# ATMEGA328.net
KiCad netlist of a schematic drawn in Altium Designer
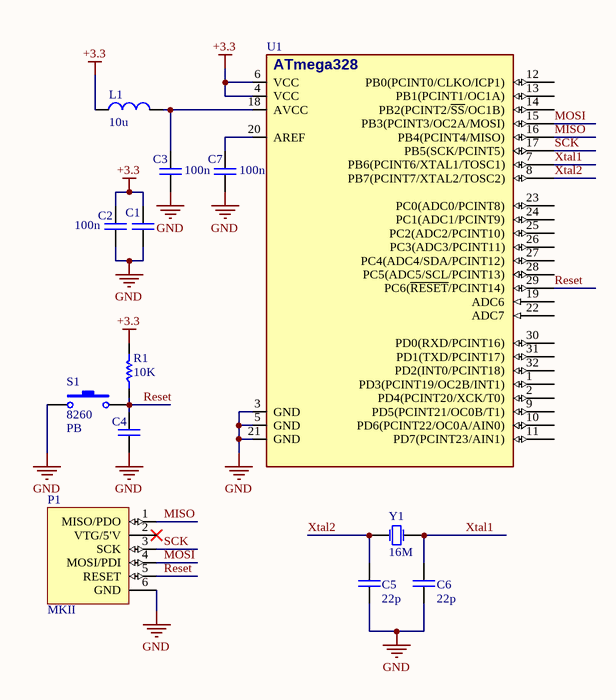
[diagram p0: ATMEGA328.SchDoc]

(export (version "E")
  (design (tool "Eeschema 10.0.6"))
  (components
    (comp (ref "C1")
      (value "100n")
      (footprint "CAP 0805/2012")
      (description "Bipolar ceramic capacitor SMD")
      (fields (field (name "VALIDATION") "Valid"))
      (libsource (lib "aKaReZa") (part "Cap_Multi_SMD_100nF_0805"))
    )
    (comp (ref "C2")
      (value "100n")
      (footprint "CAP 0805/2012")
      (description "Bipolar ceramic capacitor SMD")
      (fields (field (name "VALIDATION") "Valid"))
      (libsource (lib "aKaReZa") (part "Cap_Multi_SMD_100nF_0805"))
    )
    (comp (ref "C3")
      (value "100n")
      (footprint "CAP 0805/2012")
      (description "Bipolar ceramic capacitor SMD")
      (fields (field (name "VALIDATION") "Valid"))
      (libsource (lib "aKaReZa") (part "Cap_Multi_SMD_100nF_0805"))
    )
    (comp (ref "C4")
      (value "100n")
      (footprint "CAP 0805/2012")
      (description "Bipolar ceramic capacitor SMD")
      (fields (field (name "VALIDATION") "Valid"))
      (libsource (lib "aKaReZa") (part "Cap_Multi_SMD_100nF_0805"))
    )
    (comp (ref "C5")
      (value "22p")
      (footprint "CAP 0805/2012")
      (description "Bipolar ceramic capacitor SMD")
      (fields (field (name "VALIDATION") "Valid"))
      (libsource (lib "aKaReZa") (part "Cap_Multi_SMD_0805"))
    )
    (comp (ref "C6")
      (value "22p")
      (footprint "CAP 0805/2012")
      (description "Bipolar ceramic capacitor SMD")
      (fields (field (name "VALIDATION") "Valid"))
      (libsource (lib "aKaReZa") (part "Cap_Multi_SMD_0805"))
    )
    (comp (ref "C7")
      (value "100n")
      (footprint "CAP 0805/2012")
      (description "Bipolar ceramic capacitor SMD")
      (fields (field (name "VALIDATION") "Valid"))
      (libsource (lib "aKaReZa") (part "Cap_Multi_SMD_100nF_0805"))
    )
    (comp (ref "L1")
      (value "10u")
      (footprint "IND0805")
      (description "Inductor")
      (fields (field (name "VALIDATION") "Valid"))
      (libsource (lib "aKaReZa") (part "Ind_SMD_0805"))
    )
    (comp (ref "P1")
      (value "3x2")
      (footprint "IDC_2X3")
      (description "6 Pin Standard ISP Header For MKII")
      (fields (field (name "TYPE") "MKII") (field (name "VALIDATION") "NT"))
      (libsource (lib "aKaReZa") (part "Con_Prog_MKII_ISP"))
    )
    (comp (ref "R1")
      (value "10K")
      (footprint "RES 0805 (2012X06L)")
      (description "Resistor")
      (fields (field (name "VALIDATION") "Valid"))
      (libsource (lib "aKaReZa") (part "Res_SMD_0805"))
    )
    (comp (ref "S1")
      (value "PB")
      (footprint "SW_PB_SMD_2PIN_SPST_6X3X2")
      (description "SMT Tactile ‎Switch")
      (fields (field (name "INFLOW") "8260") (field (name "VALIDATION") "Valid"))
      (libsource (lib "aKaReZa") (part "SW_PushButton_2_SMD"))
    )
    (comp (ref "U1")
      (value "ATmega328P")
      (footprint "QFG50_48")
      (description "8-Bit AVR Microcontroller with 32K Bytes of In-System Programmable Flash Memory")
      (fields (field (name "VALIDATION") "Valid"))
      (libsource (lib "aKaReZa") (part "IC_MCU_ATmega328P_SMD"))
    )
    (comp (ref "Y1")
      (value "16M")
      (footprint "Crystal SMD")
      (description "Crystal Oscillator")
      (fields (field (name "VALIDATION") "Valid"))
      (libsource (lib "aKaReZa") (part "Other_Elec_Xtal_SMD"))
    )
  )
  (nets
    (net (code "1") (name "+3.3") (class "Default")
      (node (ref "C1") (pin "1") (pinfunction "1_1") (pintype "passive"))
      (node (ref "C2") (pin "1") (pinfunction "1_1") (pintype "passive"))
      (node (ref "L1") (pin "1") (pinfunction "1_1") (pintype "passive"))
      (node (ref "R1") (pin "2") (pinfunction "2_2") (pintype "passive"))
      (node (ref "U1") (pin "4") (pinfunction "VCC_4") (pintype "power_in"))
      (node (ref "U1") (pin "6") (pinfunction "VCC_6") (pintype "power_in"))
    )
    (net (code "2") (name "/MISO") (class "Default")
      (node (ref "P1") (pin "1") (pinfunction "MISO/PDO_1") (pintype "bidirectional"))
      (node (ref "U1") (pin "16") (pinfunction "PB4(PCINT4/MISO)_16") (pintype "bidirectional"))
    )
    (net (code "3") (name "/MOSI") (class "Default")
      (node (ref "P1") (pin "4") (pinfunction "MOSI/PDI_4") (pintype "bidirectional"))
      (node (ref "U1") (pin "15") (pinfunction "PB3(PCINT3/OC2A/MOSI)_15") (pintype "bidirectional"))
    )
    (net (code "4") (name "/Reset") (class "Default")
      (node (ref "C4") (pin "1") (pinfunction "1_1") (pintype "passive"))
      (node (ref "P1") (pin "5") (pinfunction "RESET_5") (pintype "bidirectional"))
      (node (ref "R1") (pin "1") (pinfunction "1_1") (pintype "passive"))
      (node (ref "S1") (pin "2") (pinfunction "2_2") (pintype "passive"))
      (node (ref "U1") (pin "29") (pinfunction "PC6(~{RESET}/PCINT14)_29") (pintype "bidirectional"))
    )
    (net (code "5") (name "/SCK") (class "Default")
      (node (ref "P1") (pin "3") (pinfunction "SCK_3") (pintype "bidirectional"))
      (node (ref "U1") (pin "17") (pinfunction "PB5(SCK/PCINT5)_17") (pintype "bidirectional"))
    )
    (net (code "6") (name "/Xtal1") (class "Default")
      (node (ref "C6") (pin "1") (pinfunction "1_1") (pintype "passive"))
      (node (ref "U1") (pin "7") (pinfunction "PB6(PCINT6/XTAL1/TOSC1)_7") (pintype "bidirectional"))
      (node (ref "Y1") (pin "2") (pinfunction "OSC2_2") (pintype "passive"))
    )
    (net (code "7") (name "/Xtal2") (class "Default")
      (node (ref "C5") (pin "1") (pinfunction "1_1") (pintype "passive"))
      (node (ref "U1") (pin "8") (pinfunction "PB7(PCINT7/XTAL2/TOSC2)_8") (pintype "bidirectional"))
      (node (ref "Y1") (pin "1") (pinfunction "OSC1_1") (pintype "passive"))
    )
    (net (code "8") (name "GND") (class "Default")
      (node (ref "C1") (pin "2") (pinfunction "2_2") (pintype "passive"))
      (node (ref "C2") (pin "2") (pinfunction "2_2") (pintype "passive"))
      (node (ref "C3") (pin "2") (pinfunction "2_2") (pintype "passive"))
      (node (ref "C4") (pin "2") (pinfunction "2_2") (pintype "passive"))
      (node (ref "C5") (pin "2") (pinfunction "2_2") (pintype "passive"))
      (node (ref "C6") (pin "2") (pinfunction "2_2") (pintype "passive"))
      (node (ref "C7") (pin "2") (pinfunction "2_2") (pintype "passive"))
      (node (ref "P1") (pin "6") (pinfunction "GND_6") (pintype "passive"))
      (node (ref "S1") (pin "1") (pinfunction "1_1") (pintype "passive"))
      (node (ref "U1") (pin "21") (pinfunction "GND_21") (pintype "power_in"))
      (node (ref "U1") (pin "3") (pinfunction "GND_3") (pintype "power_in"))
      (node (ref "U1") (pin "5") (pinfunction "GND_5") (pintype "power_in"))
    )
    (net (code "9") (name "Net-(U1-AREF)") (class "Default")
      (node (ref "C7") (pin "1") (pinfunction "1_1") (pintype "passive"))
      (node (ref "U1") (pin "20") (pinfunction "AREF_20") (pintype "passive"))
    )
    (net (code "10") (name "Net-(U1-AVCC)") (class "Default")
      (node (ref "C3") (pin "1") (pinfunction "1_1") (pintype "passive"))
      (node (ref "L1") (pin "2") (pinfunction "2_2") (pintype "passive"))
      (node (ref "U1") (pin "18") (pinfunction "AVCC_18") (pintype "power_in"))
    )
    (net (code "11") (name "unconnected-(P1-VTG{slash}5'V-Pad2)") (class "Default")
      (node (ref "P1") (pin "2") (pinfunction "VTG/5'V_2") (pintype "passive+no_connect"))
    )
    (net (code "12") (name "unconnected-(U1-ADC6-Pad19)") (class "Default")
      (node (ref "U1") (pin "19") (pinfunction "ADC6_19") (pintype "input"))
    )
    (net (code "13") (name "unconnected-(U1-ADC7-Pad22)") (class "Default")
      (node (ref "U1") (pin "22") (pinfunction "ADC7_22") (pintype "input"))
    )
    (net (code "14") (name "unconnected-(U1-PB0(PCINT0{slash}CLKO{slash}ICP1)-Pad12)") (class "Default")
      (node (ref "U1") (pin "12") (pinfunction "PB0(PCINT0/CLKO/ICP1)_12") (pintype "bidirectional"))
    )
    (net (code "15") (name "unconnected-(U1-PB1(PCINT1{slash}OC1A)-Pad13)") (class "Default")
      (node (ref "U1") (pin "13") (pinfunction "PB1(PCINT1/OC1A)_13") (pintype "bidirectional"))
    )
    (net (code "16") (name "unconnected-(U1-PB2(PCINT2{slash}~{SS}{slash}OC1B)-Pad14)") (class "Default")
      (node (ref "U1") (pin "14") (pinfunction "PB2(PCINT2/~{SS}/OC1B)_14") (pintype "bidirectional"))
    )
    (net (code "17") (name "unconnected-(U1-PC0(ADC0{slash}PCINT8)-Pad23)") (class "Default")
      (node (ref "U1") (pin "23") (pinfunction "PC0(ADC0/PCINT8)_23") (pintype "bidirectional"))
    )
    (net (code "18") (name "unconnected-(U1-PC1(ADC1{slash}PCINT9)-Pad24)") (class "Default")
      (node (ref "U1") (pin "24") (pinfunction "PC1(ADC1/PCINT9)_24") (pintype "bidirectional"))
    )
    (net (code "19") (name "unconnected-(U1-PC2(ADC2{slash}PCINT10)-Pad25)") (class "Default")
      (node (ref "U1") (pin "25") (pinfunction "PC2(ADC2/PCINT10)_25") (pintype "bidirectional"))
    )
    (net (code "20") (name "unconnected-(U1-PC3(ADC3{slash}PCINT11)-Pad26)") (class "Default")
      (node (ref "U1") (pin "26") (pinfunction "PC3(ADC3/PCINT11)_26") (pintype "bidirectional"))
    )
    (net (code "21") (name "unconnected-(U1-PC4(ADC4{slash}SDA{slash}PCINT12)-Pad27)") (class "Default")
      (node (ref "U1") (pin "27") (pinfunction "PC4(ADC4/SDA/PCINT12)_27") (pintype "bidirectional"))
    )
    (net (code "22") (name "unconnected-(U1-PC5(ADC5{slash}SCL{slash}PCINT13)-Pad28)") (class "Default")
      (node (ref "U1") (pin "28") (pinfunction "PC5(ADC5/SCL/PCINT13)_28") (pintype "bidirectional"))
    )
    (net (code "23") (name "unconnected-(U1-PD0(RXD{slash}PCINT16)-Pad30)") (class "Default")
      (node (ref "U1") (pin "30") (pinfunction "PD0(RXD/PCINT16)_30") (pintype "bidirectional"))
    )
    (net (code "24") (name "unconnected-(U1-PD1(TXD{slash}PCINT17)-Pad31)") (class "Default")
      (node (ref "U1") (pin "31") (pinfunction "PD1(TXD/PCINT17)_31") (pintype "bidirectional"))
    )
    (net (code "25") (name "unconnected-(U1-PD2(INT0{slash}PCINT18)-Pad32)") (class "Default")
      (node (ref "U1") (pin "32") (pinfunction "PD2(INT0/PCINT18)_32") (pintype "bidirectional"))
    )
    (net (code "26") (name "unconnected-(U1-PD3(PCINT19{slash}OC2B{slash}INT1)-Pad1)") (class "Default")
      (node (ref "U1") (pin "1") (pinfunction "PD3(PCINT19/OC2B/INT1)_1") (pintype "bidirectional"))
    )
    (net (code "27") (name "unconnected-(U1-PD4(PCINT20{slash}XCK{slash}T0)-Pad2)") (class "Default")
      (node (ref "U1") (pin "2") (pinfunction "PD4(PCINT20/XCK/T0)_2") (pintype "bidirectional"))
    )
    (net (code "28") (name "unconnected-(U1-PD5(PCINT21{slash}OC0B{slash}T1)-Pad9)") (class "Default")
      (node (ref "U1") (pin "9") (pinfunction "PD5(PCINT21/OC0B/T1)_9") (pintype "bidirectional"))
    )
    (net (code "29") (name "unconnected-(U1-PD6(PCINT22{slash}OC0A{slash}AIN0)-Pad10)") (class "Default")
      (node (ref "U1") (pin "10") (pinfunction "PD6(PCINT22/OC0A/AIN0)_10") (pintype "bidirectional"))
    )
    (net (code "30") (name "unconnected-(U1-PD7(PCINT23{slash}AIN1)-Pad11)") (class "Default")
      (node (ref "U1") (pin "11") (pinfunction "PD7(PCINT23/AIN1)_11") (pintype "bidirectional"))
    )
  )
)
